# Connecteur_SIM7000G_devbord.net
KiCad netlist of a schematic drawn in Altium Designer
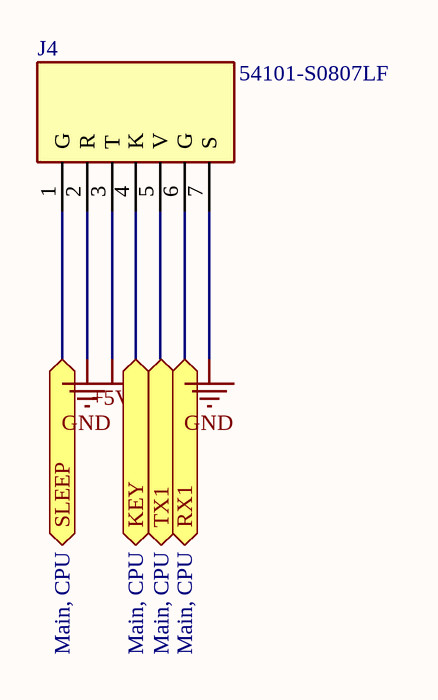
[diagram p0: Connecteur SIM7000G devbord .SchDoc]

(export (version "E")
  (design (tool "Eeschema 10.0.6"))
  (components
    (comp (ref "J4")
      (value "54101-S0807LF")
      (footprint "54101S0807LF")
      (fields (field (name "MOUSER PART NUMBER") "649-54101-S0807LF"))
      (libsource (lib "SFMproject") (part "SIM7000G CONNETEUR"))
    )
  )
  (nets
    (net (code "1") (name "+5V") (class "Default")
      (node (ref "J4") (pin "3") (pinfunction "T_3") (pintype "passive"))
    )
    (net (code "2") (name "/KEY") (class "Default")
      (node (ref "J4") (pin "4") (pinfunction "K_4") (pintype "passive"))
    )
    (net (code "3") (name "/RX1") (class "Default")
      (node (ref "J4") (pin "6") (pinfunction "G_6") (pintype "passive"))
    )
    (net (code "4") (name "/SLEEP") (class "Default")
      (node (ref "J4") (pin "1") (pinfunction "G_1") (pintype "passive"))
    )
    (net (code "5") (name "/TX1") (class "Default")
      (node (ref "J4") (pin "5") (pinfunction "V_5") (pintype "passive"))
    )
    (net (code "6") (name "GND") (class "Default")
      (node (ref "J4") (pin "2") (pinfunction "R_2") (pintype "passive"))
      (node (ref "J4") (pin "7") (pinfunction "S_7") (pintype "passive"))
    )
  )
)
